# T15_PRI_SYS_V1_5.net
KiCad netlist of a schematic drawn in EAGLE
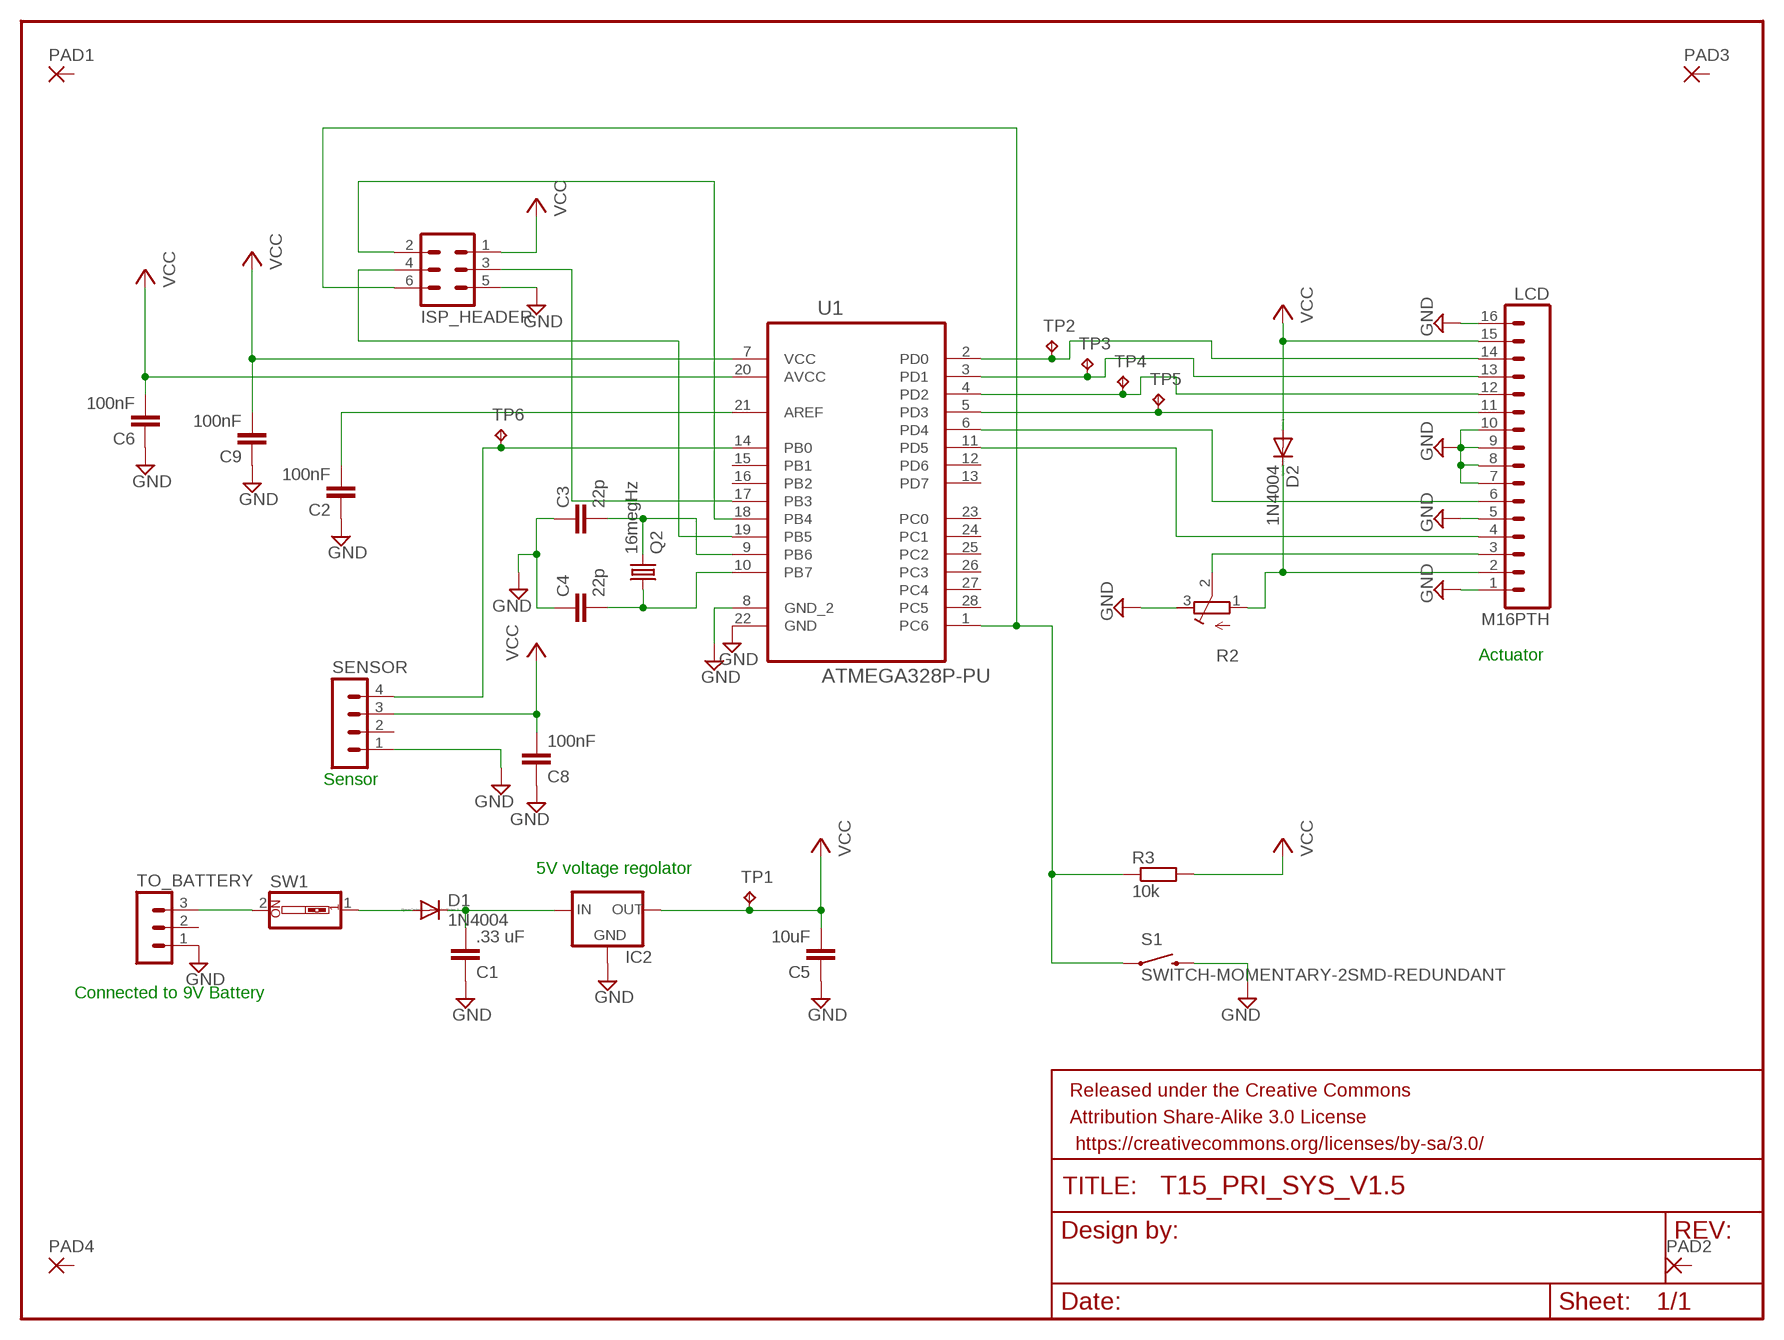
[diagram p0: schematic, sheet 1]

(export (version "E")
  (design (tool "Eeschema 10.0.6"))
  (components
    (comp (ref "C1")
      (value ".33 uF")
      (footprint "eagle-import:C025-024X044")
      (libsource (lib "eagle-import") (part "C-EU025-024X044"))
    )
    (comp (ref "C2")
      (value "100nF")
      (footprint "eagle-import:C025-024X044")
      (libsource (lib "eagle-import") (part "C-EU025-024X044"))
    )
    (comp (ref "C3")
      (value "22p")
      (footprint "eagle-import:C025-024X044")
      (libsource (lib "eagle-import") (part "C-EU025-024X044"))
    )
    (comp (ref "C4")
      (value "22p")
      (footprint "eagle-import:C025-024X044")
      (libsource (lib "eagle-import") (part "C-EU025-024X044"))
    )
    (comp (ref "C5")
      (value "10uF")
      (footprint "eagle-import:C025-024X044")
      (libsource (lib "eagle-import") (part "C-EU025-024X044"))
    )
    (comp (ref "C6")
      (value "100nF")
      (footprint "eagle-import:C025-024X044")
      (libsource (lib "eagle-import") (part "C-EU025-024X044"))
    )
    (comp (ref "C8")
      (value "100nF")
      (footprint "eagle-import:C025-024X044")
      (libsource (lib "eagle-import") (part "C-EU025-024X044"))
    )
    (comp (ref "C9")
      (value "100nF")
      (footprint "eagle-import:C025-024X044")
      (libsource (lib "eagle-import") (part "C-EU025-024X044"))
    )
    (comp (ref "D1")
      (value "1N4004")
      (footprint "eagle-import:DO41-10")
      (libsource (lib "eagle-import") (part "1N4004"))
    )
    (comp (ref "D2")
      (value "1N4004")
      (footprint "eagle-import:DO41-10")
      (libsource (lib "eagle-import") (part "1N4004"))
    )
    (comp (ref "FRAME1")
      (value "FRAME-LETTER")
      (footprint "eagle-import:CREATIVE_COMMONS")
      (libsource (lib "eagle-import") (part "FRAME-LETTER"))
    )
    (comp (ref "IC2")
      (value "78XXL")
      (footprint "eagle-import:78XXL")
      (libsource (lib "eagle-import") (part "78XXL"))
    )
    (comp (ref "ISP_HEADER")
      (value "MA03-2")
      (footprint "eagle-import:MA03-2")
      (libsource (lib "eagle-import") (part "MA03-2"))
    )
    (comp (ref "LCD")
      (value "M16PTH")
      (footprint "eagle-import:1X16")
      (libsource (lib "eagle-import") (part "M16PTH"))
    )
    (comp (ref "PAD1")
      (value "1,6/0,8")
      (footprint "eagle-import:1,6_0,8")
      (libsource (lib "eagle-import") (part "1,6/0,8"))
    )
    (comp (ref "PAD2")
      (value "1,6/0,8")
      (footprint "eagle-import:1,6_0,8")
      (libsource (lib "eagle-import") (part "1,6/0,8"))
    )
    (comp (ref "PAD3")
      (value "1,6/0,8")
      (footprint "eagle-import:1,6_0,8")
      (libsource (lib "eagle-import") (part "1,6/0,8"))
    )
    (comp (ref "PAD4")
      (value "1,6/0,8")
      (footprint "eagle-import:1,6_0,8")
      (libsource (lib "eagle-import") (part "1,6/0,8"))
    )
    (comp (ref "Q2")
      (value "16megHz")
      (footprint "eagle-import:HC49_S")
      (libsource (lib "eagle-import") (part "CRYSTALHC49S"))
    )
    (comp (ref "R2")
      (value "R-TRIMMTS63Z")
      (footprint "eagle-import:RTRIMTS63Z")
      (libsource (lib "eagle-import") (part "R-TRIMMTS63Z"))
    )
    (comp (ref "R3")
      (value "10k")
      (footprint "eagle-import:0204_5")
      (libsource (lib "eagle-import") (part "R-EU_0204/5"))
    )
    (comp (ref "S1")
      (value "SWITCH-MOMENTARY-2SMD-REDUNDANT")
      (footprint "eagle-import:TACTILE-SWITCH-SMD")
      (libsource (lib "eagle-import") (part "SWITCH-MOMENTARY-2SMD-REDUNDANT"))
    )
    (comp (ref "SENSOR")
      (value "MA04-1")
      (footprint "eagle-import:MA04-1")
      (libsource (lib "eagle-import") (part "MA04-1"))
    )
    (comp (ref "SW1")
      (value "SW_DIP-1")
      (footprint "eagle-import:EDG-01")
      (libsource (lib "eagle-import") (part "SW_DIP-1"))
    )
    (comp (ref "TO_BATTERY")
      (value "MA03-1")
      (footprint "eagle-import:MA03-1")
      (libsource (lib "eagle-import") (part "MA03-1"))
    )
    (comp (ref "TP1")
      (value "TPB1,27")
      (footprint "eagle-import:B1,27")
      (libsource (lib "eagle-import") (part "TPB1,27"))
    )
    (comp (ref "TP2")
      (value "TPB1,27")
      (footprint "eagle-import:B1,27")
      (libsource (lib "eagle-import") (part "TPB1,27"))
    )
    (comp (ref "TP3")
      (value "TPB1,27")
      (footprint "eagle-import:B1,27")
      (libsource (lib "eagle-import") (part "TPB1,27"))
    )
    (comp (ref "TP4")
      (value "TPB1,27")
      (footprint "eagle-import:B1,27")
      (libsource (lib "eagle-import") (part "TPB1,27"))
    )
    (comp (ref "TP5")
      (value "TPB1,27")
      (footprint "eagle-import:B1,27")
      (libsource (lib "eagle-import") (part "TPB1,27"))
    )
    (comp (ref "TP6")
      (value "TPB1,27")
      (footprint "eagle-import:B1,27")
      (libsource (lib "eagle-import") (part "TPB1,27"))
    )
    (comp (ref "U1")
      (value "ATMEGA328P-PU")
      (footprint "eagle-import:DIP254P762X457-28")
      (libsource (lib "eagle-import") (part "ATMEGA328P-PU"))
    )
  )
  (nets
    (net (code "1") (name "GND") (class "Default")
      (node (ref "C1") (pin "1") (pinfunction "1_1") (pintype "passive"))
      (node (ref "C2") (pin "1") (pinfunction "1_1") (pintype "passive"))
      (node (ref "C3") (pin "1") (pinfunction "1_1") (pintype "passive"))
      (node (ref "C4") (pin "1") (pinfunction "1_1") (pintype "passive"))
      (node (ref "C5") (pin "1") (pinfunction "1_1") (pintype "passive"))
      (node (ref "C6") (pin "1") (pinfunction "1_1") (pintype "passive"))
      (node (ref "C8") (pin "1") (pinfunction "1_1") (pintype "passive"))
      (node (ref "C9") (pin "1") (pinfunction "1_1") (pintype "passive"))
      (node (ref "IC2") (pin "GND") (pinfunction "GND_GND") (pintype "input"))
      (node (ref "ISP_HEADER") (pin "5") (pinfunction "5_5") (pintype "passive"))
      (node (ref "LCD") (pin "1") (pinfunction "1_1") (pintype "passive"))
      (node (ref "LCD") (pin "10") (pinfunction "10_10") (pintype "passive"))
      (node (ref "LCD") (pin "16") (pinfunction "16_16") (pintype "passive"))
      (node (ref "LCD") (pin "5") (pinfunction "5_5") (pintype "passive"))
      (node (ref "LCD") (pin "7") (pinfunction "7_7") (pintype "passive"))
      (node (ref "LCD") (pin "8") (pinfunction "8_8") (pintype "passive"))
      (node (ref "LCD") (pin "9") (pinfunction "9_9") (pintype "passive"))
      (node (ref "R2") (pin "3") (pinfunction "E_3") (pintype "passive"))
      (node (ref "S1") (pin "3") (pinfunction "2_3") (pintype "passive"))
      (node (ref "S1") (pin "4") (pinfunction "2_4") (pintype "passive"))
      (node (ref "SENSOR") (pin "1") (pinfunction "1_1") (pintype "passive"))
      (node (ref "TO_BATTERY") (pin "1") (pinfunction "1_1") (pintype "passive"))
      (node (ref "U1") (pin "22") (pinfunction "GND_22") (pintype "passive"))
      (node (ref "U1") (pin "8") (pinfunction "GND_2_8") (pintype "passive"))
    )
    (net (code "2") (name "Net-(C1-Pad2)") (class "Default")
      (node (ref "C1") (pin "2") (pinfunction "2_2") (pintype "passive"))
      (node (ref "D1") (pin "C") (pinfunction "C_C") (pintype "passive"))
      (node (ref "IC2") (pin "IN") (pinfunction "IN_IN") (pintype "input"))
    )
    (net (code "3") (name "Net-(D1-PadA)") (class "Default")
      (node (ref "D1") (pin "A") (pinfunction "A_A") (pintype "passive"))
      (node (ref "SW1") (pin "1") (pinfunction "1_1") (pintype "passive"))
    )
    (net (code "4") (name "Net-(R2-A)") (class "Default")
      (node (ref "D2") (pin "C") (pinfunction "C_C") (pintype "passive"))
      (node (ref "LCD") (pin "2") (pinfunction "2_2") (pintype "passive"))
      (node (ref "R2") (pin "1") (pinfunction "A_1") (pintype "passive"))
    )
    (net (code "5") (name "Net-(R2-S)") (class "Default")
      (node (ref "LCD") (pin "3") (pinfunction "3_3") (pintype "passive"))
      (node (ref "R2") (pin "2") (pinfunction "S_2") (pintype "passive"))
    )
    (net (code "6") (name "Net-(SW1-Pad2)") (class "Default")
      (node (ref "SW1") (pin "2") (pinfunction "2_2") (pintype "passive"))
      (node (ref "TO_BATTERY") (pin "3") (pinfunction "3_3") (pintype "passive"))
    )
    (net (code "7") (name "Net-(U1-AREF)") (class "Default")
      (node (ref "C2") (pin "2") (pinfunction "2_2") (pintype "passive"))
      (node (ref "U1") (pin "21") (pinfunction "AREF_21") (pintype "input"))
    )
    (net (code "8") (name "Net-(U1-PB0)") (class "Default")
      (node (ref "SENSOR") (pin "4") (pinfunction "4_4") (pintype "passive"))
      (node (ref "TP6") (pin "TP") (pinfunction "TP_TP") (pintype "input"))
      (node (ref "U1") (pin "14") (pinfunction "PB0_14") (pintype "bidirectional"))
    )
    (net (code "9") (name "Net-(U1-PB3)") (class "Default")
      (node (ref "ISP_HEADER") (pin "3") (pinfunction "3_3") (pintype "passive"))
      (node (ref "U1") (pin "17") (pinfunction "PB3_17") (pintype "bidirectional"))
    )
    (net (code "10") (name "Net-(U1-PB4)") (class "Default")
      (node (ref "ISP_HEADER") (pin "2") (pinfunction "2_2") (pintype "passive"))
      (node (ref "U1") (pin "18") (pinfunction "PB4_18") (pintype "bidirectional"))
    )
    (net (code "11") (name "Net-(U1-PB5)") (class "Default")
      (node (ref "ISP_HEADER") (pin "4") (pinfunction "4_4") (pintype "passive"))
      (node (ref "U1") (pin "19") (pinfunction "PB5_19") (pintype "bidirectional"))
    )
    (net (code "12") (name "Net-(U1-PB6)") (class "Default")
      (node (ref "C3") (pin "2") (pinfunction "2_2") (pintype "passive"))
      (node (ref "Q2") (pin "2") (pinfunction "2_2") (pintype "passive"))
      (node (ref "U1") (pin "9") (pinfunction "PB6_9") (pintype "bidirectional"))
    )
    (net (code "13") (name "Net-(U1-PB7)") (class "Default")
      (node (ref "C4") (pin "2") (pinfunction "2_2") (pintype "passive"))
      (node (ref "Q2") (pin "1") (pinfunction "1_1") (pintype "passive"))
      (node (ref "U1") (pin "10") (pinfunction "PB7_10") (pintype "bidirectional"))
    )
    (net (code "14") (name "Net-(U1-PC6)") (class "Default")
      (node (ref "ISP_HEADER") (pin "6") (pinfunction "6_6") (pintype "passive"))
      (node (ref "R3") (pin "1") (pinfunction "1_1") (pintype "passive"))
      (node (ref "S1") (pin "1") (pinfunction "1_1") (pintype "passive"))
      (node (ref "S1") (pin "2") (pinfunction "1_2") (pintype "passive"))
      (node (ref "U1") (pin "1") (pinfunction "PC6_1") (pintype "bidirectional"))
    )
    (net (code "15") (name "Net-(U1-PD0)") (class "Default")
      (node (ref "LCD") (pin "14") (pinfunction "14_14") (pintype "passive"))
      (node (ref "TP2") (pin "TP") (pinfunction "TP_TP") (pintype "input"))
      (node (ref "U1") (pin "2") (pinfunction "PD0_2") (pintype "bidirectional"))
    )
    (net (code "16") (name "Net-(U1-PD1)") (class "Default")
      (node (ref "LCD") (pin "13") (pinfunction "13_13") (pintype "passive"))
      (node (ref "TP3") (pin "TP") (pinfunction "TP_TP") (pintype "input"))
      (node (ref "U1") (pin "3") (pinfunction "PD1_3") (pintype "bidirectional"))
    )
    (net (code "17") (name "Net-(U1-PD2)") (class "Default")
      (node (ref "LCD") (pin "12") (pinfunction "12_12") (pintype "passive"))
      (node (ref "TP4") (pin "TP") (pinfunction "TP_TP") (pintype "input"))
      (node (ref "U1") (pin "4") (pinfunction "PD2_4") (pintype "bidirectional"))
    )
    (net (code "18") (name "Net-(U1-PD3)") (class "Default")
      (node (ref "LCD") (pin "11") (pinfunction "11_11") (pintype "passive"))
      (node (ref "TP5") (pin "TP") (pinfunction "TP_TP") (pintype "input"))
      (node (ref "U1") (pin "5") (pinfunction "PD3_5") (pintype "bidirectional"))
    )
    (net (code "19") (name "Net-(U1-PD4)") (class "Default")
      (node (ref "LCD") (pin "6") (pinfunction "6_6") (pintype "passive"))
      (node (ref "U1") (pin "6") (pinfunction "PD4_6") (pintype "bidirectional"))
    )
    (net (code "20") (name "Net-(U1-PD5)") (class "Default")
      (node (ref "LCD") (pin "4") (pinfunction "4_4") (pintype "passive"))
      (node (ref "U1") (pin "11") (pinfunction "PD5_11") (pintype "bidirectional"))
    )
    (net (code "21") (name "VCC") (class "Default")
      (node (ref "C5") (pin "2") (pinfunction "2_2") (pintype "passive"))
      (node (ref "C6") (pin "2") (pinfunction "2_2") (pintype "passive"))
      (node (ref "C8") (pin "2") (pinfunction "2_2") (pintype "passive"))
      (node (ref "C9") (pin "2") (pinfunction "2_2") (pintype "passive"))
      (node (ref "D2") (pin "A") (pinfunction "A_A") (pintype "passive"))
      (node (ref "IC2") (pin "OUT") (pinfunction "OUT_OUT") (pintype "passive"))
      (node (ref "ISP_HEADER") (pin "1") (pinfunction "1_1") (pintype "passive"))
      (node (ref "LCD") (pin "15") (pinfunction "15_15") (pintype "passive"))
      (node (ref "R3") (pin "2") (pinfunction "2_2") (pintype "passive"))
      (node (ref "SENSOR") (pin "3") (pinfunction "3_3") (pintype "passive"))
      (node (ref "TP1") (pin "TP") (pinfunction "TP_TP") (pintype "input"))
      (node (ref "U1") (pin "20") (pinfunction "AVCC_20") (pintype "power_in"))
      (node (ref "U1") (pin "7") (pinfunction "VCC_7") (pintype "power_in"))
    )
    (net (code "22") (name "unconnected-(PAD1-P-Pad1)") (class "Default")
      (node (ref "PAD1") (pin "1") (pinfunction "P_1") (pintype "passive"))
    )
    (net (code "23") (name "unconnected-(PAD2-P-Pad1)") (class "Default")
      (node (ref "PAD2") (pin "1") (pinfunction "P_1") (pintype "passive"))
    )
    (net (code "24") (name "unconnected-(PAD3-P-Pad1)") (class "Default")
      (node (ref "PAD3") (pin "1") (pinfunction "P_1") (pintype "passive"))
    )
    (net (code "25") (name "unconnected-(PAD4-P-Pad1)") (class "Default")
      (node (ref "PAD4") (pin "1") (pinfunction "P_1") (pintype "passive"))
    )
    (net (code "26") (name "unconnected-(SENSOR-Pad2)") (class "Default")
      (node (ref "SENSOR") (pin "2") (pinfunction "2_2") (pintype "passive"))
    )
    (net (code "27") (name "unconnected-(TO_BATTERY-Pad2)") (class "Default")
      (node (ref "TO_BATTERY") (pin "2") (pinfunction "2_2") (pintype "passive"))
    )
    (net (code "28") (name "unconnected-(U1-PB1-Pad15)") (class "Default")
      (node (ref "U1") (pin "15") (pinfunction "PB1_15") (pintype "bidirectional"))
    )
    (net (code "29") (name "unconnected-(U1-PB2-Pad16)") (class "Default")
      (node (ref "U1") (pin "16") (pinfunction "PB2_16") (pintype "bidirectional"))
    )
    (net (code "30") (name "unconnected-(U1-PC0-Pad23)") (class "Default")
      (node (ref "U1") (pin "23") (pinfunction "PC0_23") (pintype "bidirectional"))
    )
    (net (code "31") (name "unconnected-(U1-PC1-Pad24)") (class "Default")
      (node (ref "U1") (pin "24") (pinfunction "PC1_24") (pintype "bidirectional"))
    )
    (net (code "32") (name "unconnected-(U1-PC2-Pad25)") (class "Default")
      (node (ref "U1") (pin "25") (pinfunction "PC2_25") (pintype "bidirectional"))
    )
    (net (code "33") (name "unconnected-(U1-PC3-Pad26)") (class "Default")
      (node (ref "U1") (pin "26") (pinfunction "PC3_26") (pintype "bidirectional"))
    )
    (net (code "34") (name "unconnected-(U1-PC4-Pad27)") (class "Default")
      (node (ref "U1") (pin "27") (pinfunction "PC4_27") (pintype "bidirectional"))
    )
    (net (code "35") (name "unconnected-(U1-PC5-Pad28)") (class "Default")
      (node (ref "U1") (pin "28") (pinfunction "PC5_28") (pintype "bidirectional"))
    )
    (net (code "36") (name "unconnected-(U1-PD6-Pad12)") (class "Default")
      (node (ref "U1") (pin "12") (pinfunction "PD6_12") (pintype "bidirectional"))
    )
    (net (code "37") (name "unconnected-(U1-PD7-Pad13)") (class "Default")
      (node (ref "U1") (pin "13") (pinfunction "PD7_13") (pintype "bidirectional"))
    )
  )
)
